# oak_pcb.net
KiCad netlist of a schematic drawn in EAGLE
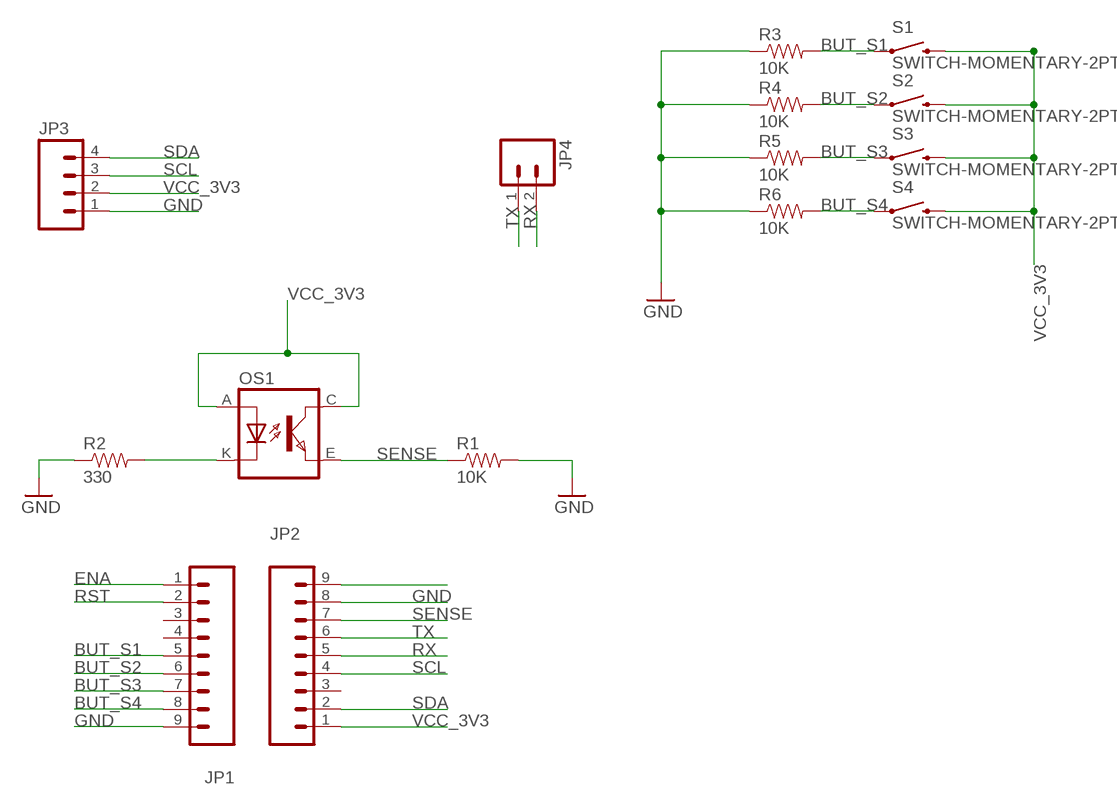
[diagram p0: schematic, sheet 1]

(export (version "E")
  (design (tool "Eeschema 10.0.6"))
  (components
    (comp (ref "JP1")
      (value "M09LOCK")
      (footprint "eagle-import:1X09_LOCK")
      (libsource (lib "eagle-import") (part "M09LOCK"))
    )
    (comp (ref "JP2")
      (value "M09LOCK")
      (footprint "eagle-import:1X09_LOCK")
      (libsource (lib "eagle-import") (part "M09LOCK"))
    )
    (comp (ref "JP3")
      (value "M04LOCK")
      (footprint "eagle-import:1X04_LOCK")
      (libsource (lib "eagle-import") (part "M04LOCK"))
    )
    (comp (ref "JP4")
      (value "M02LOCK")
      (footprint "eagle-import:1X02_LOCK")
      (libsource (lib "eagle-import") (part "M02LOCK"))
    )
    (comp (ref "OS1")
      (value "TCRT5000")
      (footprint "eagle-import:TCRT5000")
      (libsource (lib "eagle-import") (part "TCRT5000"))
    )
    (comp (ref "R1")
      (value "10K")
      (footprint "eagle-import:AXIAL-0.5")
      (libsource (lib "eagle-import") (part "RESISTORPTH-1/2W"))
    )
    (comp (ref "R2")
      (value "330")
      (footprint "eagle-import:AXIAL-0.5")
      (libsource (lib "eagle-import") (part "RESISTORPTH-1/2W"))
    )
    (comp (ref "R3")
      (value "10K")
      (footprint "eagle-import:AXIAL-0.4")
      (libsource (lib "eagle-import") (part "RESISTORPTH-1/4W"))
    )
    (comp (ref "R4")
      (value "10K")
      (footprint "eagle-import:AXIAL-0.4")
      (libsource (lib "eagle-import") (part "RESISTORPTH-1/4W"))
    )
    (comp (ref "R5")
      (value "10K")
      (footprint "eagle-import:AXIAL-0.4")
      (libsource (lib "eagle-import") (part "RESISTORPTH-1/4W"))
    )
    (comp (ref "R6")
      (value "10K")
      (footprint "eagle-import:AXIAL-0.4")
      (libsource (lib "eagle-import") (part "RESISTORPTH-1/4W"))
    )
    (comp (ref "S1")
      (value "SWITCH-MOMENTARY-2PTH")
      (footprint "eagle-import:TACTILE-PTH")
      (libsource (lib "eagle-import") (part "SWITCH-MOMENTARY-2PTH"))
    )
    (comp (ref "S2")
      (value "SWITCH-MOMENTARY-2PTH")
      (footprint "eagle-import:TACTILE-PTH")
      (libsource (lib "eagle-import") (part "SWITCH-MOMENTARY-2PTH"))
    )
    (comp (ref "S3")
      (value "SWITCH-MOMENTARY-2PTH")
      (footprint "eagle-import:TACTILE-PTH")
      (libsource (lib "eagle-import") (part "SWITCH-MOMENTARY-2PTH"))
    )
    (comp (ref "S4")
      (value "SWITCH-MOMENTARY-2PTH")
      (footprint "eagle-import:TACTILE-PTH")
      (libsource (lib "eagle-import") (part "SWITCH-MOMENTARY-2PTH"))
    )
  )
  (nets
    (net (code "1") (name "/BUT_S1") (class "Default")
      (node (ref "JP1") (pin "5") (pinfunction "5_5") (pintype "passive"))
      (node (ref "R3") (pin "P$2") (pinfunction "2_P$2") (pintype "passive"))
      (node (ref "S1") (pin "1") (pinfunction "1_1") (pintype "passive"))
    )
    (net (code "2") (name "/BUT_S2") (class "Default")
      (node (ref "JP1") (pin "6") (pinfunction "6_6") (pintype "passive"))
      (node (ref "R4") (pin "P$2") (pinfunction "2_P$2") (pintype "passive"))
      (node (ref "S2") (pin "1") (pinfunction "1_1") (pintype "passive"))
    )
    (net (code "3") (name "/BUT_S3") (class "Default")
      (node (ref "JP1") (pin "7") (pinfunction "7_7") (pintype "passive"))
      (node (ref "R5") (pin "P$2") (pinfunction "2_P$2") (pintype "passive"))
      (node (ref "S3") (pin "1") (pinfunction "1_1") (pintype "passive"))
    )
    (net (code "4") (name "/BUT_S4") (class "Default")
      (node (ref "JP1") (pin "8") (pinfunction "8_8") (pintype "passive"))
      (node (ref "R6") (pin "P$2") (pinfunction "2_P$2") (pintype "passive"))
      (node (ref "S4") (pin "1") (pinfunction "1_1") (pintype "passive"))
    )
    (net (code "5") (name "/ENA") (class "Default")
      (node (ref "JP1") (pin "1") (pinfunction "1_1") (pintype "passive"))
    )
    (net (code "6") (name "/RST") (class "Default")
      (node (ref "JP1") (pin "2") (pinfunction "2_2") (pintype "passive"))
    )
    (net (code "7") (name "/RX") (class "Default")
      (node (ref "JP2") (pin "5") (pinfunction "5_5") (pintype "passive"))
      (node (ref "JP4") (pin "2") (pinfunction "2_2") (pintype "passive"))
    )
    (net (code "8") (name "/SCL") (class "Default")
      (node (ref "JP2") (pin "4") (pinfunction "4_4") (pintype "passive"))
      (node (ref "JP3") (pin "3") (pinfunction "3_3") (pintype "passive"))
    )
    (net (code "9") (name "/SDA") (class "Default")
      (node (ref "JP2") (pin "2") (pinfunction "2_2") (pintype "passive"))
      (node (ref "JP3") (pin "4") (pinfunction "4_4") (pintype "passive"))
    )
    (net (code "10") (name "/SENSE") (class "Default")
      (node (ref "JP2") (pin "7") (pinfunction "7_7") (pintype "passive"))
      (node (ref "OS1") (pin "E") (pinfunction "EMITTER_E") (pintype "passive"))
      (node (ref "R1") (pin "P$1") (pinfunction "1_P$1") (pintype "passive"))
    )
    (net (code "11") (name "/TX") (class "Default")
      (node (ref "JP2") (pin "6") (pinfunction "6_6") (pintype "passive"))
      (node (ref "JP4") (pin "1") (pinfunction "1_1") (pintype "passive"))
    )
    (net (code "12") (name "/VCC_3V3") (class "Default")
      (node (ref "JP2") (pin "1") (pinfunction "1_1") (pintype "passive"))
      (node (ref "JP3") (pin "2") (pinfunction "2_2") (pintype "passive"))
      (node (ref "OS1") (pin "A") (pinfunction "ANODE_A") (pintype "passive"))
      (node (ref "OS1") (pin "C") (pinfunction "COLLECTOR_C") (pintype "passive"))
      (node (ref "S1") (pin "3") (pinfunction "2_3") (pintype "passive"))
      (node (ref "S2") (pin "3") (pinfunction "2_3") (pintype "passive"))
      (node (ref "S3") (pin "3") (pinfunction "2_3") (pintype "passive"))
      (node (ref "S4") (pin "3") (pinfunction "2_3") (pintype "passive"))
    )
    (net (code "13") (name "GND") (class "Default")
      (node (ref "JP1") (pin "9") (pinfunction "9_9") (pintype "passive"))
      (node (ref "JP2") (pin "8") (pinfunction "8_8") (pintype "passive"))
      (node (ref "JP3") (pin "1") (pinfunction "1_1") (pintype "passive"))
      (node (ref "R1") (pin "P$2") (pinfunction "2_P$2") (pintype "passive"))
      (node (ref "R2") (pin "P$1") (pinfunction "1_P$1") (pintype "passive"))
      (node (ref "R3") (pin "P$1") (pinfunction "1_P$1") (pintype "passive"))
      (node (ref "R4") (pin "P$1") (pinfunction "1_P$1") (pintype "passive"))
      (node (ref "R5") (pin "P$1") (pinfunction "1_P$1") (pintype "passive"))
      (node (ref "R6") (pin "P$1") (pinfunction "1_P$1") (pintype "passive"))
    )
    (net (code "14") (name "Net-(OS1-CATHODE)") (class "Default")
      (node (ref "OS1") (pin "K") (pinfunction "CATHODE_K") (pintype "passive"))
      (node (ref "R2") (pin "P$2") (pinfunction "2_P$2") (pintype "passive"))
    )
    (net (code "15") (name "unconnected-(JP1-Pad3)") (class "Default")
      (node (ref "JP1") (pin "3") (pinfunction "3_3") (pintype "passive"))
    )
    (net (code "16") (name "unconnected-(JP1-Pad4)") (class "Default")
      (node (ref "JP1") (pin "4") (pinfunction "4_4") (pintype "passive"))
    )
    (net (code "17") (name "unconnected-(JP2-Pad3)") (class "Default")
      (node (ref "JP2") (pin "3") (pinfunction "3_3") (pintype "passive"))
    )
    (net (code "18") (name "unconnected-(JP2-Pad9)") (class "Default")
      (node (ref "JP2") (pin "9") (pinfunction "9_9") (pintype "passive"))
    )
  )
)
